# Sch_front.net
KiCad netlist of a schematic drawn in Altium Designer
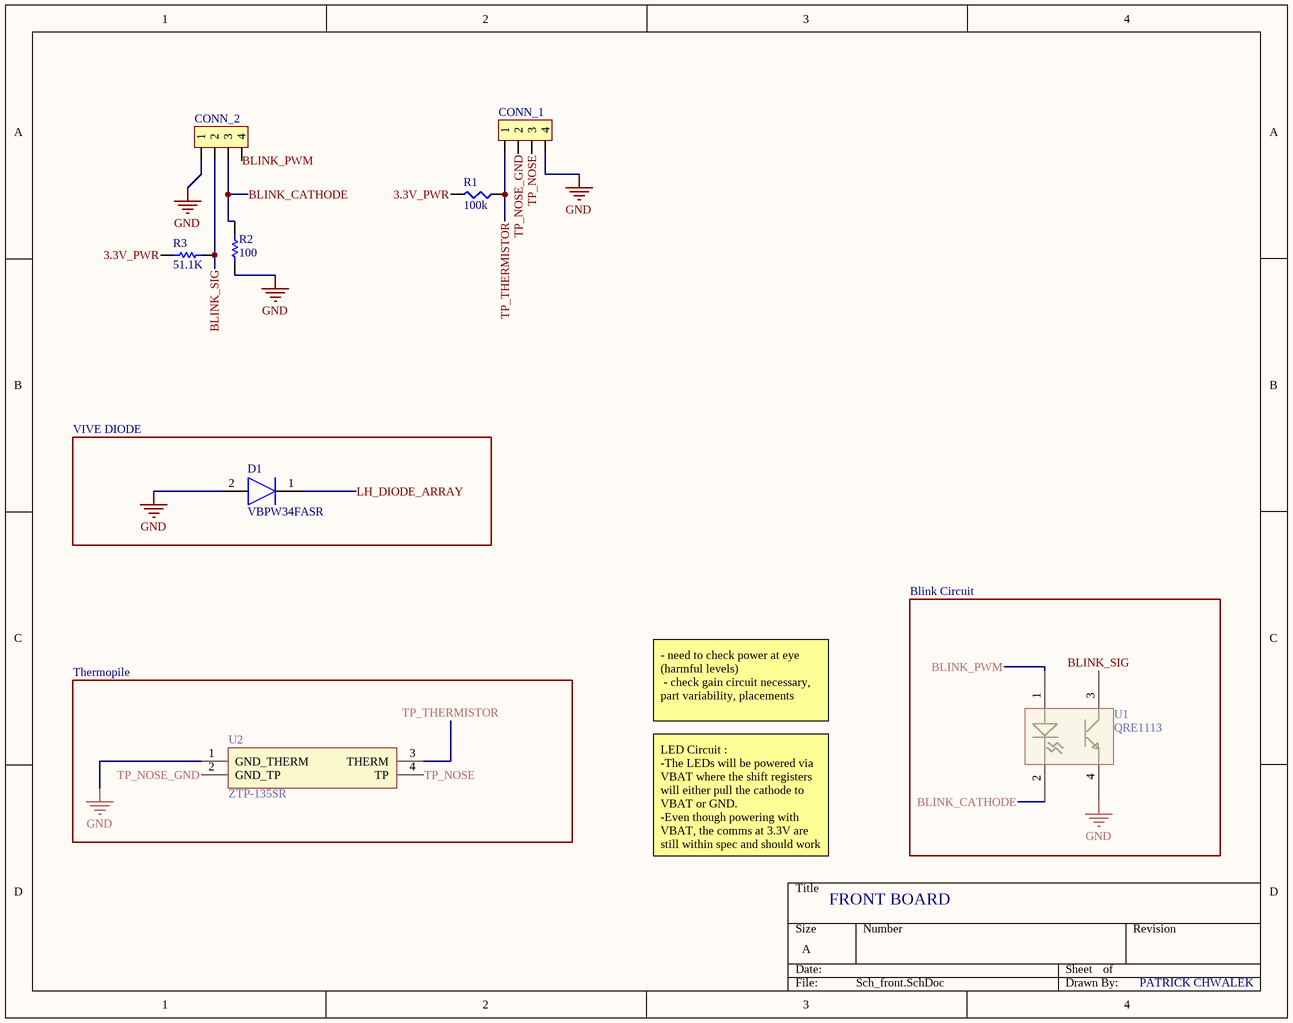
[diagram p0: Sch_front.SchDoc]

(export (version "E")
  (design (tool "Eeschema 10.0.6"))
  (components
    (comp (ref "CONN_1")
      (value "THERMO")
      (footprint "4_pos_1mm_header")
      (libsource (lib "schematic_components") (part "4_pin_1mm_header"))
    )
    (comp (ref "CONN_2")
      (value "BLINK")
      (footprint "4_pos_1mm_header")
      (libsource (lib "schematic_components") (part "4_pin_1mm_header"))
    )
    (comp (ref "D1")
      (value "VBPW34FASR")
      (footprint "VBPW34FAS")
      (description "Diode")
      (fields (field (name "MOUSER PART NUMBER") "782-VBPW34FASR") (field (name "RS PART NUMBER") "7689401"))
      (libsource (lib "*") (part "VBPW34FASR"))
    )
    (comp (ref "R1")
      (value "100k")
      (footprint "SMD-0402-RES")
      (description "RES SMD 100K OHM 5% 1/10W 0402")
      (fields (field (name "PART NUMBER") "ERJ-2GEJ104X") (field (name "DIGI-KEY PART NUMBER") "P100KJCT-ND"))
      (libsource (lib "Panasonic_ERJ_0402") (part "ERJ-2GEJ104X"))
    )
    (comp (ref "R2") (value "100") (footprint "SMD-0402C") (libsource (lib "bdm") (part "Resistor")))
    (comp (ref "R3") (value "51.1K") (footprint "SMD-0402-RES") (libsource (lib "bdm") (part "Resistor")))
    (comp (ref "U1")
      (value "QRE1113")
      (footprint "QRE1113_DIP")
      (description "IR Emitter and Receiver")
      (libsource (lib "Schematic Components") (part "QRE1113"))
    )
    (comp (ref "U2")
      (value "ZTP-135SR")
      (footprint "ZTP-135SR")
      (description "Undefined or Miscellaneous")
      (fields (field (name "MOUSER PART NUMBER") "527-ZTP-135SR"))
      (libsource (lib "SamacSys") (part "ZTP-135SR"))
    )
  )
  (nets
    (net (code "1") (name "/3.3V_PWR") (class "Default")
      (node (ref "R1") (pin "2") (pinfunction "2_2") (pintype "passive"))
      (node (ref "R3") (pin "2") (pinfunction "2_2") (pintype "passive"))
    )
    (net (code "2") (name "/BLINK_CATHODE") (class "Default")
      (node (ref "CONN_2") (pin "3") (pinfunction "3_3") (pintype "passive"))
      (node (ref "R2") (pin "2") (pinfunction "2_2") (pintype "passive"))
      (node (ref "U1") (pin "2") (pinfunction "2_2") (pintype "passive"))
    )
    (net (code "3") (name "/BLINK_PWM") (class "Default")
      (node (ref "CONN_2") (pin "4") (pinfunction "4_4") (pintype "passive"))
      (node (ref "U1") (pin "1") (pinfunction "1_1") (pintype "passive"))
    )
    (net (code "4") (name "/BLINK_SIG") (class "Default")
      (node (ref "CONN_2") (pin "2") (pinfunction "2_2") (pintype "passive"))
      (node (ref "R3") (pin "1") (pinfunction "1_1") (pintype "passive"))
      (node (ref "U1") (pin "3") (pinfunction "3_3") (pintype "passive"))
    )
    (net (code "5") (name "/LH_DIODE_ARRAY") (class "Default")
      (node (ref "D1") (pin "1") (pinfunction "A_1") (pintype "passive"))
    )
    (net (code "6") (name "/TP_NOSE") (class "Default")
      (node (ref "CONN_1") (pin "3") (pinfunction "3_3") (pintype "passive"))
      (node (ref "U2") (pin "4") (pinfunction "TP_4") (pintype "passive"))
    )
    (net (code "7") (name "/TP_NOSE_GND") (class "Default")
      (node (ref "CONN_1") (pin "2") (pinfunction "2_2") (pintype "passive"))
      (node (ref "U2") (pin "2") (pinfunction "GND_TP_2") (pintype "passive"))
    )
    (net (code "8") (name "/TP_THERMISTOR") (class "Default")
      (node (ref "CONN_1") (pin "1") (pinfunction "1_1") (pintype "passive"))
      (node (ref "R1") (pin "1") (pinfunction "1_1") (pintype "passive"))
      (node (ref "U2") (pin "3") (pinfunction "THERM_3") (pintype "passive"))
    )
    (net (code "9") (name "GND") (class "Default")
      (node (ref "CONN_1") (pin "4") (pinfunction "4_4") (pintype "passive"))
      (node (ref "CONN_2") (pin "1") (pinfunction "1_1") (pintype "passive"))
      (node (ref "D1") (pin "2") (pinfunction "K_2") (pintype "passive"))
      (node (ref "R2") (pin "1") (pinfunction "1_1") (pintype "passive"))
      (node (ref "U1") (pin "4") (pinfunction "4_4") (pintype "passive"))
      (node (ref "U2") (pin "1") (pinfunction "GND_THERM_1") (pintype "passive"))
    )
  )
)
